# DC_DC_Converter.net
KiCad netlist of a schematic drawn in Altium Designer
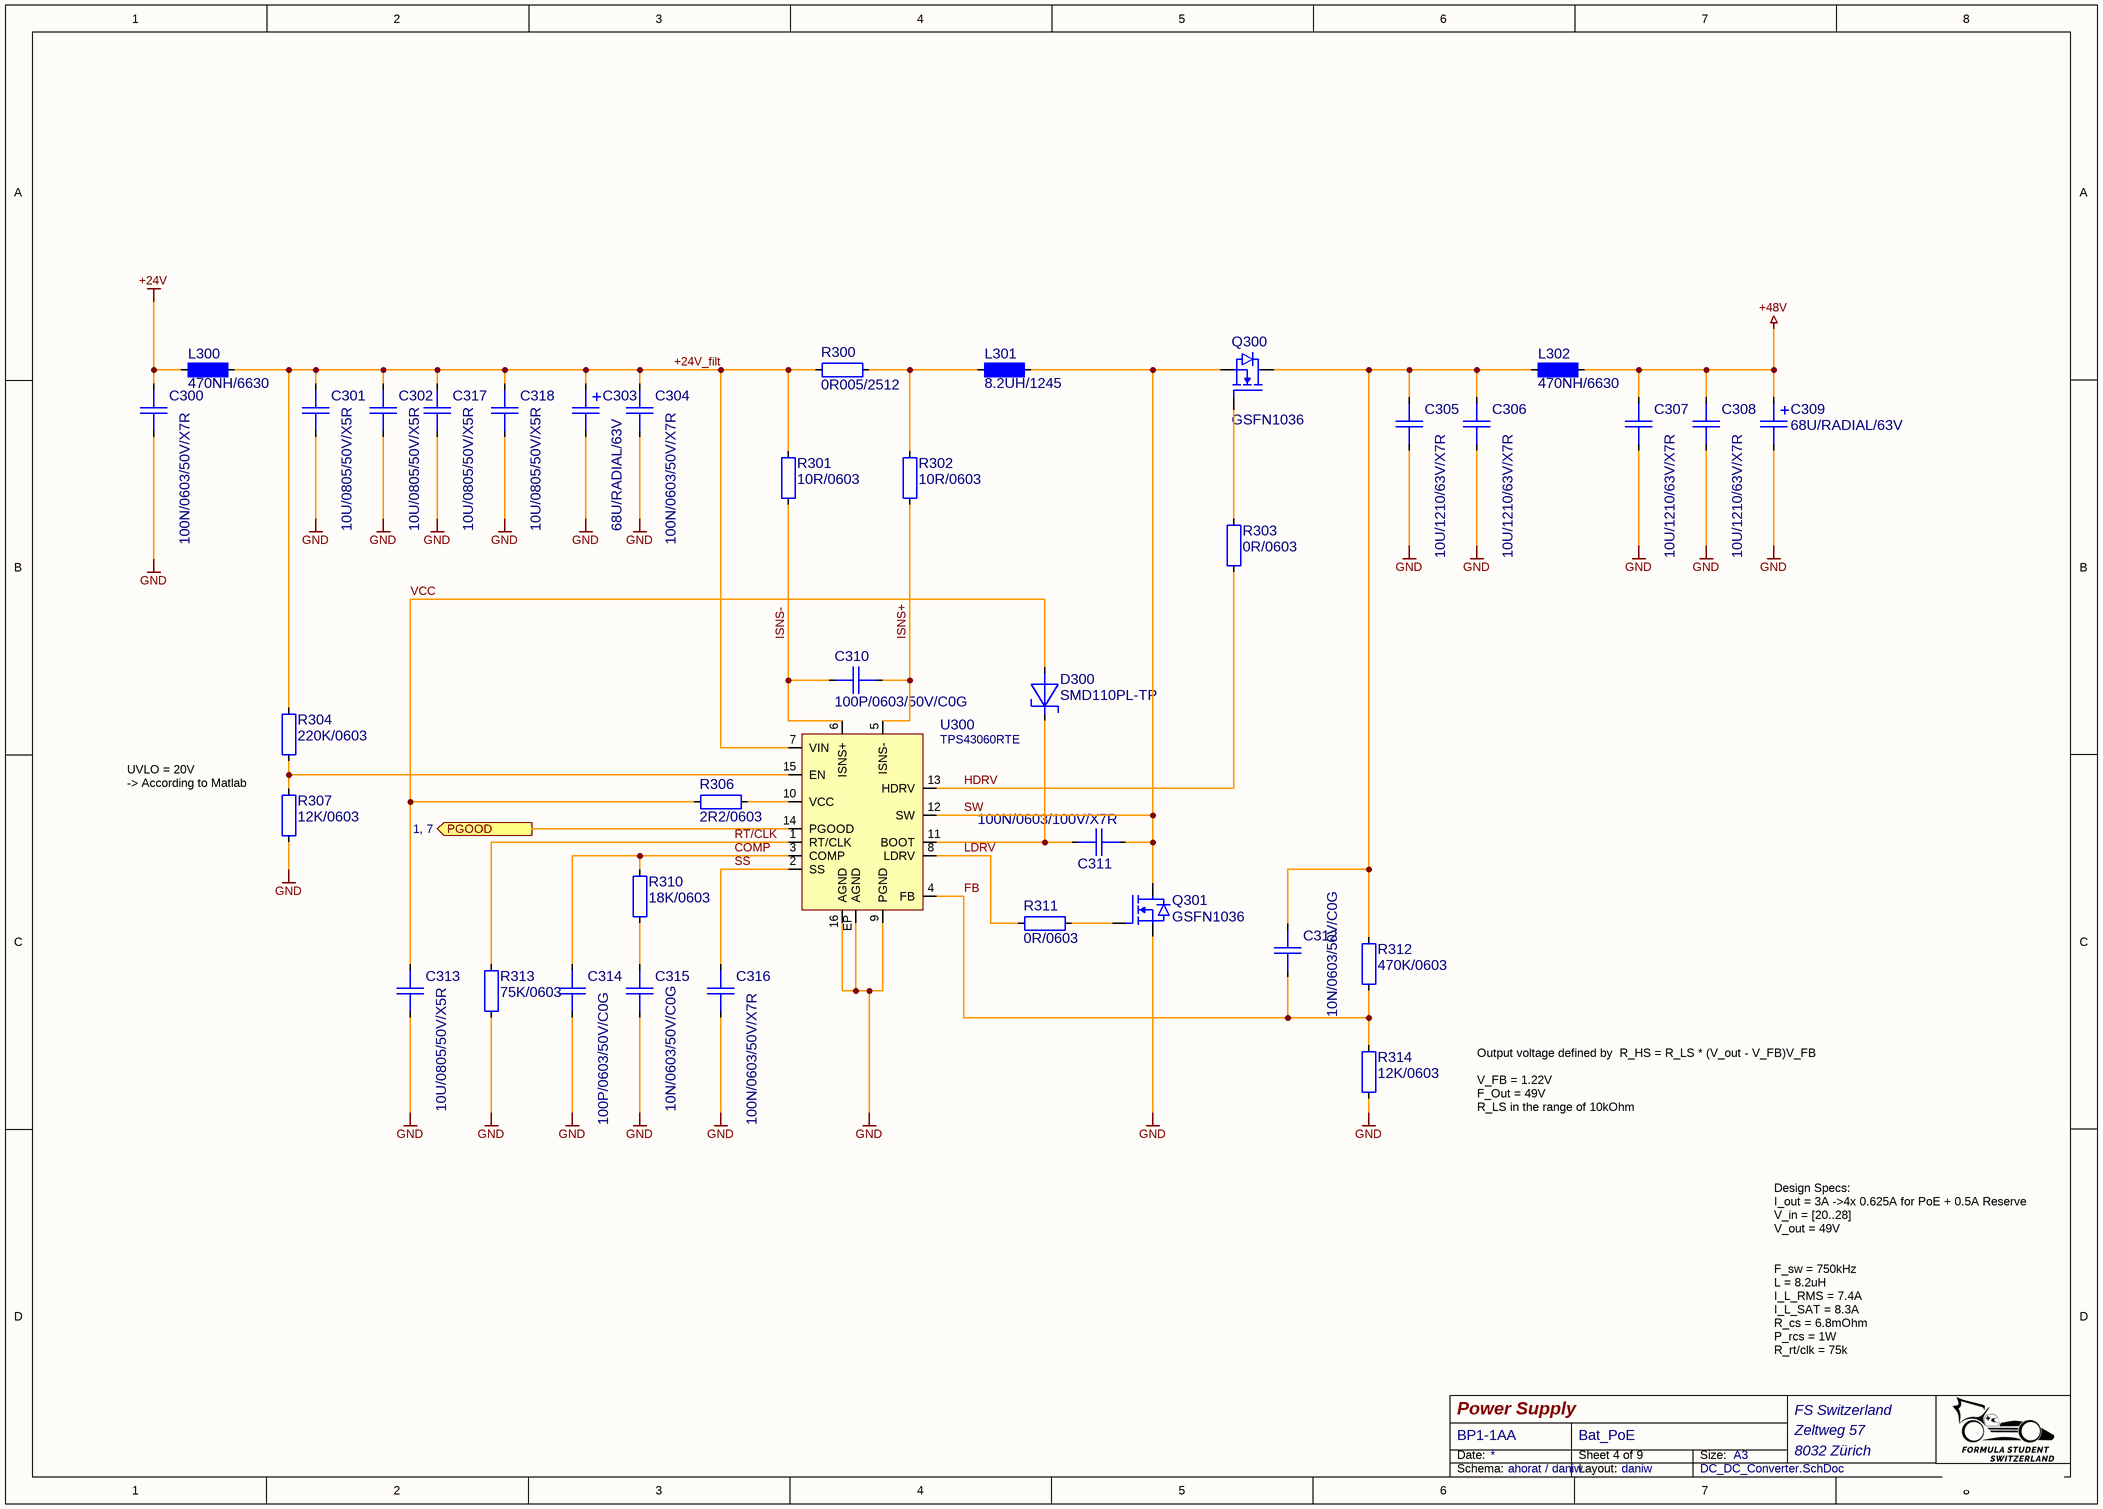
[diagram p0: DC_DC_Converter.SchDoc]

(export (version "E")
  (design (tool "Eeschema 10.0.6"))
  (components
    (comp (ref "C300")
      (value "100N/0603/50V/X7R")
      (footprint "CAP0603_X7R")
      (description "CAP SM 0603 100nF 50V X7R")
      (fields (field (name "MANUFACTURER") "GENERIC"))
      (libsource (lib "daniw_altium_lib") (part "C"))
    )
    (comp (ref "C301")
      (value "10U/0805/50V/X5R")
      (footprint "CAP0805_X7R")
      (description "CAP SM 0805 10uF 50V X5R")
      (fields (field (name "MANUFACTURER") "GENERIC"))
      (libsource (lib "daniw_altium_lib") (part "C"))
    )
    (comp (ref "C302")
      (value "10U/0805/50V/X5R")
      (footprint "CAP0805_X7R")
      (description "CAP SM 0805 10uF 50V X5R")
      (fields (field (name "MANUFACTURER") "GENERIC"))
      (libsource (lib "daniw_altium_lib") (part "C"))
    )
    (comp (ref "C303")
      (value "68U/RADIAL/63V")
      (footprint "CAP350P80X130")
      (description "CAP THT 8C130 68UF ELKO 63V")
      (fields (field (name "MANUFACTURER") "GENERIC"))
      (libsource (lib "daniw_altium_lib") (part "C_ELEC"))
    )
    (comp (ref "C304")
      (value "100N/0603/50V/X7R")
      (footprint "CAP0603_X7R")
      (description "CAP SM 0603 100nF 50V X7R")
      (fields (field (name "MANUFACTURER") "GENERIC"))
      (libsource (lib "daniw_altium_lib") (part "C"))
    )
    (comp (ref "C305")
      (value "10U/1210/63V/X7R")
      (footprint "CAP1210_X7R")
      (description "CAP SM 1210 10uF 63V X7R")
      (fields (field (name "MANUFACTURER") "GENERIC"))
      (libsource (lib "daniw_altium_lib") (part "C"))
    )
    (comp (ref "C306")
      (value "10U/1210/63V/X7R")
      (footprint "CAP1210_X7R")
      (description "CAP SM 1210 10uF 63V X7R")
      (fields (field (name "MANUFACTURER") "GENERIC"))
      (libsource (lib "daniw_altium_lib") (part "C"))
    )
    (comp (ref "C307")
      (value "10U/1210/63V/X7R")
      (footprint "CAP1210_X7R")
      (description "CAP SM 1210 10uF 63V X7R")
      (fields (field (name "MANUFACTURER") "GENERIC"))
      (libsource (lib "daniw_altium_lib") (part "C"))
    )
    (comp (ref "C308")
      (value "10U/1210/63V/X7R")
      (footprint "CAP1210_X7R")
      (description "CAP SM 1210 10uF 63V X7R")
      (fields (field (name "MANUFACTURER") "GENERIC"))
      (libsource (lib "daniw_altium_lib") (part "C"))
    )
    (comp (ref "C309")
      (value "68U/RADIAL/63V")
      (footprint "CAP350P80X130")
      (description "CAP THT 8C130 68UF ELKO 63V")
      (fields (field (name "MANUFACTURER") "GENERIC"))
      (libsource (lib "daniw_altium_lib") (part "C_ELEC"))
    )
    (comp (ref "C310")
      (value "100P/0603/50V/C0G")
      (footprint "CAP0603_C0G")
      (description "CAP SM 0603 100pF 50V C0G")
      (fields (field (name "MANUFACTURER") "GENERIC"))
      (libsource (lib "daniw_altium_lib") (part "C"))
    )
    (comp (ref "C311")
      (value "100N/0603/100V/X7R")
      (footprint "CAP0603_X7R")
      (description "CAP SM 0603 100nF 100V X7R")
      (fields (field (name "MANUFACTURER") "GENERIC"))
      (libsource (lib "daniw_altium_lib") (part "C"))
    )
    (comp (ref "C312")
      (value "10N/0603/50V/C0G")
      (footprint "CAP0603_C0G")
      (description "CAP SM 0603 10nF 50V C0G")
      (fields (field (name "MANUFACTURER") "GENERIC"))
      (libsource (lib "daniw_altium_lib") (part "C"))
    )
    (comp (ref "C313")
      (value "10U/0805/50V/X5R")
      (footprint "CAP0805_X7R")
      (description "CAP SM 0805 10uF 50V X5R")
      (fields (field (name "MANUFACTURER") "GENERIC"))
      (libsource (lib "daniw_altium_lib") (part "C"))
    )
    (comp (ref "C314")
      (value "100P/0603/50V/C0G")
      (footprint "CAP0603_C0G")
      (description "CAP SM 0603 100pF 50V C0G")
      (fields (field (name "MANUFACTURER") "GENERIC"))
      (libsource (lib "daniw_altium_lib") (part "C"))
    )
    (comp (ref "C315")
      (value "10N/0603/50V/C0G")
      (footprint "CAP0603_C0G")
      (description "CAP SM 0603 10nF 50V C0G")
      (fields (field (name "MANUFACTURER") "GENERIC"))
      (libsource (lib "daniw_altium_lib") (part "C"))
    )
    (comp (ref "C316")
      (value "100N/0603/50V/X7R")
      (footprint "CAP0603_X7R")
      (description "CAP SM 0603 100nF 50V X7R")
      (fields (field (name "MANUFACTURER") "GENERIC"))
      (libsource (lib "daniw_altium_lib") (part "C"))
    )
    (comp (ref "C317")
      (value "10U/0805/50V/X5R")
      (footprint "CAP0805_X7R")
      (description "CAP SM 0805 10uF 50V X5R")
      (fields (field (name "MANUFACTURER") "GENERIC"))
      (libsource (lib "daniw_altium_lib") (part "C"))
    )
    (comp (ref "C318")
      (value "10U/0805/50V/X5R")
      (footprint "CAP0805_X7R")
      (description "CAP SM 0805 10uF 50V X5R")
      (fields (field (name "MANUFACTURER") "GENERIC"))
      (libsource (lib "daniw_altium_lib") (part "C"))
    )
    (comp (ref "D300")
      (value "SMD110PL-TP")
      (footprint "SOD3718X125")
      (description "Schottky 100 V 1A Oberflächenmontage SOD-123FL")
      (fields (field (name "MANUFACTURER") "Micro Commercial Co"))
      (libsource (lib "daniw_altium_lib") (part "D_Schottky"))
    )
    (comp (ref "L300")
      (value "470NH/6630")
      (footprint "INDM660730X30")
      (description "FIXED IND 470NH 16.5 A 5.5 MOHM SMD")
      (fields (field (name "MANUFACTURER") "GENERIC"))
      (libsource (lib "daniw_altium_lib") (part "L"))
    )
    (comp (ref "L301")
      (value "8.2UH/1245")
      (footprint "INDM126126X47")
      (description "FIXED IND 8.2UH  11.5 A 21.5 MOHM SMD")
      (fields (field (name "MANUFACTURER") "GENERIC"))
      (libsource (lib "daniw_altium_lib") (part "L"))
    )
    (comp (ref "L302")
      (value "470NH/6630")
      (footprint "INDM660730X30")
      (description "FIXED IND 470NH 16.5 A 5.5 MOHM SMD")
      (fields (field (name "MANUFACTURER") "GENERIC"))
      (libsource (lib "daniw_altium_lib") (part "L"))
    )
    (comp (ref "Q300")
      (value "GSFN1036")
      (footprint "SON065P330X330X075-5-TH245X175")
      (description "N-Kanal 100 V 35 A (Tc) 52W (Tc) Oberflächenmontage 8-PPAK (3,1x3,05)")
      (fields (field (name "MANUFACTURER") "Good-Ark Semiconductor"))
      (libsource (lib "daniw_altium_lib") (part "MOSFET N"))
    )
    (comp (ref "Q301")
      (value "GSFN1036")
      (footprint "SON065P330X330X075-5-TH245X175")
      (description "N-Kanal 100 V 35 A (Tc) 52W (Tc) Oberflächenmontage 8-PPAK (3,1x3,05)")
      (fields (field (name "MANUFACTURER") "Good-Ark Semiconductor"))
      (libsource (lib "daniw_altium_lib") (part "MOSFET N"))
    )
    (comp (ref "R300")
      (value "0R005/2512")
      (footprint "R2512-0.65-WW")
      (description "RES SM 2512 0R005")
      (fields (field (name "MANUFACTURER") "GENERIC"))
      (libsource (lib "daniw_altium_lib") (part "R"))
    )
    (comp (ref "R301")
      (value "10R/0603")
      (footprint "R0603-0.40-WW")
      (description "RES SM 0603 10R")
      (fields (field (name "MANUFACTURER") "GENERIC"))
      (libsource (lib "daniw_altium_lib") (part "R"))
    )
    (comp (ref "R302")
      (value "10R/0603")
      (footprint "R0603-0.40-WW")
      (description "RES SM 0603 10R")
      (fields (field (name "MANUFACTURER") "GENERIC"))
      (libsource (lib "daniw_altium_lib") (part "R"))
    )
    (comp (ref "R303")
      (value "0R/0603")
      (footprint "R0603-0.40-WW")
      (description "RES SM 0603 0R")
      (fields (field (name "MANUFACTURER") "GENERIC"))
      (libsource (lib "daniw_altium_lib") (part "R"))
    )
    (comp (ref "R304")
      (value "220K/0603")
      (footprint "R0603-0.40-WW")
      (description "RES SM 0603 220K")
      (fields (field (name "MANUFACTURER") "GENERIC"))
      (libsource (lib "daniw_altium_lib") (part "R"))
    )
    (comp (ref "R306")
      (value "2R2/0603")
      (footprint "R0603-0.40-WW")
      (description "RES SM 0603 2R2")
      (fields (field (name "MANUFACTURER") "GENERIC"))
      (libsource (lib "daniw_altium_lib") (part "R"))
    )
    (comp (ref "R307")
      (value "12K/0603")
      (footprint "R0603-0.40-WW")
      (description "RES SM 0603 12K")
      (fields (field (name "MANUFACTURER") "GENERIC"))
      (libsource (lib "daniw_altium_lib") (part "R"))
    )
    (comp (ref "R310")
      (value "18K/0603")
      (footprint "R0603-0.40-WW")
      (description "RES SM 0603 18K")
      (fields (field (name "MANUFACTURER") "GENERIC"))
      (libsource (lib "daniw_altium_lib") (part "R"))
    )
    (comp (ref "R311")
      (value "0R/0603")
      (footprint "R0603-0.40-WW")
      (description "RES SM 0603 0R")
      (fields (field (name "MANUFACTURER") "GENERIC"))
      (libsource (lib "daniw_altium_lib") (part "R"))
    )
    (comp (ref "R312")
      (value "470K/0603")
      (footprint "R0603-0.40-WW")
      (description "RES SM 0603 470K")
      (fields (field (name "MANUFACTURER") "GENERIC"))
      (libsource (lib "daniw_altium_lib") (part "R"))
    )
    (comp (ref "R313")
      (value "75K/0603")
      (footprint "R0603-0.40-WW")
      (description "RES SM 0603 75K")
      (fields (field (name "MANUFACTURER") "GENERIC"))
      (libsource (lib "daniw_altium_lib") (part "R"))
    )
    (comp (ref "R314")
      (value "12K/0603")
      (footprint "R0603-0.40-WW")
      (description "RES SM 0603 12K")
      (fields (field (name "MANUFACTURER") "GENERIC"))
      (libsource (lib "daniw_altium_lib") (part "R"))
    )
    (comp (ref "U300")
      (value "TPS43060RTE")
      (footprint "QFN050P300X300X080-16-TH120X80")
      (description "TPS4306x Low Quiescent Current Synchronous Boost DC-DC Controller With Wide VIN Range")
      (fields (field (name "MANUFACTURER") "Texas Instruments"))
      (libsource (lib "daniw_altium_lib") (part "TPS43060RTE"))
    )
  )
  (nets
    (net (code "1") (name "+24V") (class "Default")
      (node (ref "C300") (pin "1") (pinfunction "1_1") (pintype "passive"))
      (node (ref "L300") (pin "1") (pinfunction "1_1") (pintype "passive"))
    )
    (net (code "2") (name "+48V") (class "Default")
      (node (ref "C307") (pin "1") (pinfunction "1_1") (pintype "passive"))
      (node (ref "C308") (pin "1") (pinfunction "1_1") (pintype "passive"))
      (node (ref "C309") (pin "1") (pinfunction "1_1") (pintype "passive"))
      (node (ref "L302") (pin "2") (pinfunction "2_2") (pintype "passive"))
    )
    (net (code "3") (name "/+24V_filt") (class "Default")
      (node (ref "C301") (pin "1") (pinfunction "1_1") (pintype "passive"))
      (node (ref "C302") (pin "1") (pinfunction "1_1") (pintype "passive"))
      (node (ref "C303") (pin "1") (pinfunction "1_1") (pintype "passive"))
      (node (ref "C304") (pin "2") (pinfunction "2_2") (pintype "passive"))
      (node (ref "C317") (pin "1") (pinfunction "1_1") (pintype "passive"))
      (node (ref "C318") (pin "1") (pinfunction "1_1") (pintype "passive"))
      (node (ref "L300") (pin "2") (pinfunction "2_2") (pintype "passive"))
      (node (ref "R300") (pin "1") (pinfunction "1_1") (pintype "passive"))
      (node (ref "R301") (pin "1") (pinfunction "1_1") (pintype "passive"))
      (node (ref "R304") (pin "1") (pinfunction "1_1") (pintype "passive"))
      (node (ref "U300") (pin "7") (pinfunction "VIN_7") (pintype "passive"))
    )
    (net (code "4") (name "/COMP") (class "Default")
      (node (ref "C314") (pin "1") (pinfunction "1_1") (pintype "passive"))
      (node (ref "R310") (pin "1") (pinfunction "1_1") (pintype "passive"))
      (node (ref "U300") (pin "3") (pinfunction "COMP_3") (pintype "passive"))
    )
    (net (code "5") (name "/FB") (class "Default")
      (node (ref "C312") (pin "2") (pinfunction "2_2") (pintype "passive"))
      (node (ref "R312") (pin "2") (pinfunction "2_2") (pintype "passive"))
      (node (ref "R314") (pin "1") (pinfunction "1_1") (pintype "passive"))
      (node (ref "U300") (pin "4") (pinfunction "FB_4") (pintype "passive"))
    )
    (net (code "6") (name "/HDRV") (class "Default")
      (node (ref "R303") (pin "1") (pinfunction "1_1") (pintype "passive"))
      (node (ref "U300") (pin "13") (pinfunction "HDRV_13") (pintype "passive"))
    )
    (net (code "7") (name "/ISNS+") (class "Default")
      (node (ref "C310") (pin "2") (pinfunction "2_2") (pintype "passive"))
      (node (ref "R302") (pin "2") (pinfunction "2_2") (pintype "passive"))
      (node (ref "U300") (pin "5") (pinfunction "ISNS-_5") (pintype "passive"))
    )
    (net (code "8") (name "/ISNS-") (class "Default")
      (node (ref "C310") (pin "1") (pinfunction "1_1") (pintype "passive"))
      (node (ref "R301") (pin "2") (pinfunction "2_2") (pintype "passive"))
      (node (ref "U300") (pin "6") (pinfunction "ISNS+_6") (pintype "passive"))
    )
    (net (code "9") (name "/LDRV") (class "Default")
      (node (ref "R311") (pin "1") (pinfunction "1_1") (pintype "passive"))
      (node (ref "U300") (pin "8") (pinfunction "LDRV_8") (pintype "passive"))
    )
    (net (code "10") (name "/PGOOD") (class "Default")
      (node (ref "U300") (pin "14") (pinfunction "PGOOD_14") (pintype "passive"))
    )
    (net (code "11") (name "/RT{slash}CLK") (class "Default")
      (node (ref "R313") (pin "1") (pinfunction "1_1") (pintype "passive"))
      (node (ref "U300") (pin "1") (pinfunction "RT/CLK_1") (pintype "passive"))
    )
    (net (code "12") (name "/SS") (class "Default")
      (node (ref "C316") (pin "1") (pinfunction "1_1") (pintype "passive"))
      (node (ref "U300") (pin "2") (pinfunction "SS_2") (pintype "passive"))
    )
    (net (code "13") (name "/SW") (class "Default")
      (node (ref "C311") (pin "2") (pinfunction "2_2") (pintype "passive"))
      (node (ref "L301") (pin "2") (pinfunction "2_2") (pintype "passive"))
      (node (ref "Q300") (pin "S") (pinfunction "SOURCE_S") (pintype "passive"))
      (node (ref "Q301") (pin "D") (pinfunction "DRAIN_D") (pintype "passive"))
      (node (ref "U300") (pin "12") (pinfunction "SW_12") (pintype "passive"))
    )
    (net (code "14") (name "/VCC") (class "Default")
      (node (ref "C313") (pin "1") (pinfunction "1_1") (pintype "passive"))
      (node (ref "D300") (pin "2") (pinfunction "2_2") (pintype "passive"))
      (node (ref "R306") (pin "1") (pinfunction "1_1") (pintype "passive"))
    )
    (net (code "15") (name "GND") (class "Default")
      (node (ref "C300") (pin "2") (pinfunction "2_2") (pintype "passive"))
      (node (ref "C301") (pin "2") (pinfunction "2_2") (pintype "passive"))
      (node (ref "C302") (pin "2") (pinfunction "2_2") (pintype "passive"))
      (node (ref "C303") (pin "2") (pinfunction "2_2") (pintype "passive"))
      (node (ref "C304") (pin "1") (pinfunction "1_1") (pintype "passive"))
      (node (ref "C305") (pin "2") (pinfunction "2_2") (pintype "passive"))
      (node (ref "C306") (pin "2") (pinfunction "2_2") (pintype "passive"))
      (node (ref "C307") (pin "2") (pinfunction "2_2") (pintype "passive"))
      (node (ref "C308") (pin "2") (pinfunction "2_2") (pintype "passive"))
      (node (ref "C309") (pin "2") (pinfunction "2_2") (pintype "passive"))
      (node (ref "C313") (pin "2") (pinfunction "2_2") (pintype "passive"))
      (node (ref "C314") (pin "2") (pinfunction "2_2") (pintype "passive"))
      (node (ref "C315") (pin "2") (pinfunction "2_2") (pintype "passive"))
      (node (ref "C316") (pin "2") (pinfunction "2_2") (pintype "passive"))
      (node (ref "C317") (pin "2") (pinfunction "2_2") (pintype "passive"))
      (node (ref "C318") (pin "2") (pinfunction "2_2") (pintype "passive"))
      (node (ref "Q301") (pin "S") (pinfunction "SOURCE_S") (pintype "passive"))
      (node (ref "R307") (pin "2") (pinfunction "2_2") (pintype "passive"))
      (node (ref "R313") (pin "2") (pinfunction "2_2") (pintype "passive"))
      (node (ref "R314") (pin "2") (pinfunction "2_2") (pintype "passive"))
      (node (ref "U300") (pin "16") (pinfunction "AGND_16") (pintype "passive"))
      (node (ref "U300") (pin "9") (pinfunction "PGND_9") (pintype "passive"))
      (node (ref "U300") (pin "EP") (pinfunction "AGND_EP") (pintype "passive"))
    )
    (net (code "16") (name "Net-(C315-Pad1)") (class "Default")
      (node (ref "C315") (pin "1") (pinfunction "1_1") (pintype "passive"))
      (node (ref "R310") (pin "2") (pinfunction "2_2") (pintype "passive"))
    )
    (net (code "17") (name "Net-(L301-Pad1)") (class "Default")
      (node (ref "L301") (pin "1") (pinfunction "1_1") (pintype "passive"))
      (node (ref "R300") (pin "2") (pinfunction "2_2") (pintype "passive"))
      (node (ref "R302") (pin "1") (pinfunction "1_1") (pintype "passive"))
    )
    (net (code "18") (name "Net-(Q300-DRAIN)") (class "Default")
      (node (ref "C305") (pin "1") (pinfunction "1_1") (pintype "passive"))
      (node (ref "C306") (pin "1") (pinfunction "1_1") (pintype "passive"))
      (node (ref "C312") (pin "1") (pinfunction "1_1") (pintype "passive"))
      (node (ref "L302") (pin "1") (pinfunction "1_1") (pintype "passive"))
      (node (ref "Q300") (pin "D") (pinfunction "DRAIN_D") (pintype "passive"))
      (node (ref "R312") (pin "1") (pinfunction "1_1") (pintype "passive"))
    )
    (net (code "19") (name "Net-(Q300-GATE)") (class "Default")
      (node (ref "Q300") (pin "G") (pinfunction "GATE_G") (pintype "passive"))
      (node (ref "R303") (pin "2") (pinfunction "2_2") (pintype "passive"))
    )
    (net (code "20") (name "Net-(Q301-GATE)") (class "Default")
      (node (ref "Q301") (pin "G") (pinfunction "GATE_G") (pintype "passive"))
      (node (ref "R311") (pin "2") (pinfunction "2_2") (pintype "passive"))
    )
    (net (code "21") (name "Net-(U300-BOOT)") (class "Default")
      (node (ref "C311") (pin "1") (pinfunction "1_1") (pintype "passive"))
      (node (ref "D300") (pin "1") (pinfunction "1_1") (pintype "passive"))
      (node (ref "U300") (pin "11") (pinfunction "BOOT_11") (pintype "passive"))
    )
    (net (code "22") (name "Net-(U300-EN)") (class "Default")
      (node (ref "R304") (pin "2") (pinfunction "2_2") (pintype "passive"))
      (node (ref "R307") (pin "1") (pinfunction "1_1") (pintype "passive"))
      (node (ref "U300") (pin "15") (pinfunction "EN_15") (pintype "passive"))
    )
    (net (code "23") (name "Net-(U300-VCC)") (class "Default")
      (node (ref "R306") (pin "2") (pinfunction "2_2") (pintype "passive"))
      (node (ref "U300") (pin "10") (pinfunction "VCC_10") (pintype "passive"))
    )
  )
)
